# 002_ESP32.net
KiCad netlist of a schematic drawn in Altium Designer
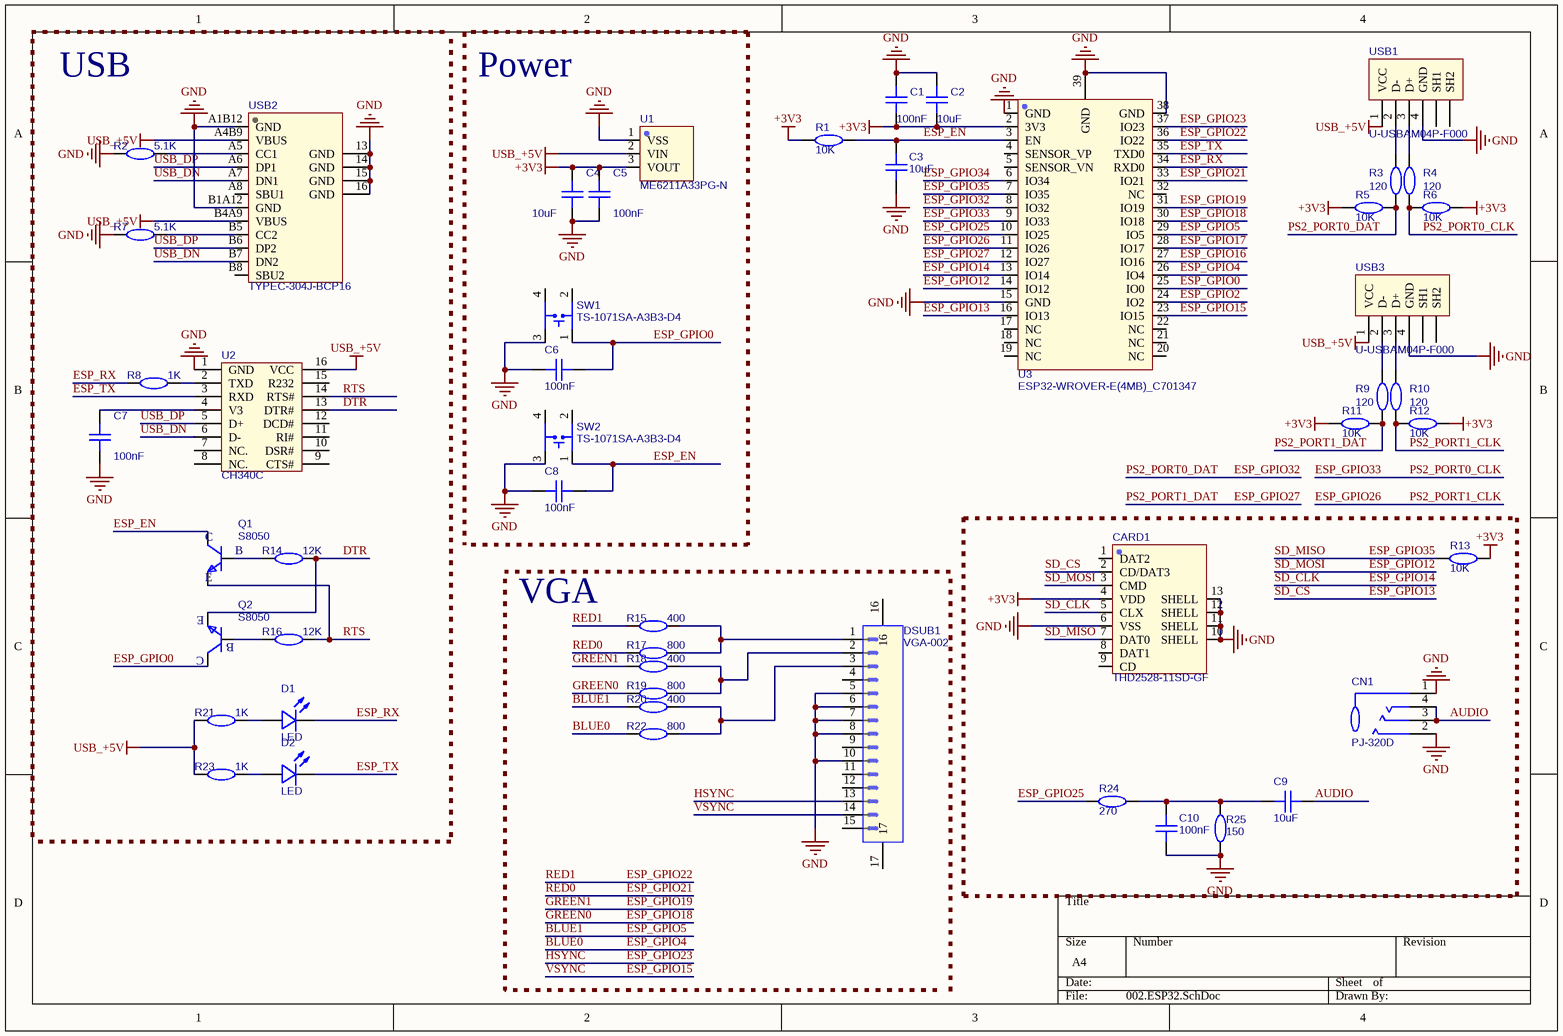
[diagram p0: 002.ESP32.SchDoc]

(export (version "E")
  (design (tool "Eeschema 10.0.6"))
  (components
    (comp (ref "C1")
      (value "100nF")
      (footprint "C0603")
      (fields
        (field (name "BOM_SUPPLIER PART") "C325469")
        (field (name "BOM_MANUFACTURER PART") "CC0603GRNPO9BN200")
        (field (name "CONTRIBUTOR") "LCSC")
      )
      (libsource (lib "miscpcb") (part "CAP_0603"))
    )
    (comp (ref "C2")
      (value "10uF")
      (footprint "C0603")
      (fields
        (field (name "BOM_SUPPLIER PART") "C325469")
        (field (name "BOM_MANUFACTURER PART") "CC0603GRNPO9BN200")
        (field (name "CONTRIBUTOR") "LCSC")
      )
      (libsource (lib "miscpcb") (part "CAP_0603"))
    )
    (comp (ref "C3")
      (value "10uF")
      (footprint "C0603")
      (fields
        (field (name "BOM_SUPPLIER PART") "C325469")
        (field (name "BOM_MANUFACTURER PART") "CC0603GRNPO9BN200")
        (field (name "CONTRIBUTOR") "LCSC")
      )
      (libsource (lib "miscpcb") (part "CAP_0603"))
    )
    (comp (ref "C4")
      (value "10uF")
      (footprint "C0603")
      (fields
        (field (name "BOM_SUPPLIER PART") "C325469")
        (field (name "BOM_MANUFACTURER PART") "CC0603GRNPO9BN200")
        (field (name "CONTRIBUTOR") "LCSC")
      )
      (libsource (lib "miscpcb") (part "CAP_0603"))
    )
    (comp (ref "C5")
      (value "100nF")
      (footprint "C0603")
      (fields
        (field (name "BOM_SUPPLIER PART") "C325469")
        (field (name "BOM_MANUFACTURER PART") "CC0603GRNPO9BN200")
        (field (name "CONTRIBUTOR") "LCSC")
      )
      (libsource (lib "miscpcb") (part "CAP_0603"))
    )
    (comp (ref "C6")
      (value "100nF")
      (footprint "C0603")
      (fields
        (field (name "BOM_SUPPLIER PART") "C325469")
        (field (name "BOM_MANUFACTURER PART") "CC0603GRNPO9BN200")
        (field (name "CONTRIBUTOR") "LCSC")
      )
      (libsource (lib "miscpcb") (part "CAP_0603"))
    )
    (comp (ref "C7")
      (value "100nF")
      (footprint "C0603")
      (fields
        (field (name "BOM_SUPPLIER PART") "C325469")
        (field (name "BOM_MANUFACTURER PART") "CC0603GRNPO9BN200")
        (field (name "CONTRIBUTOR") "LCSC")
      )
      (libsource (lib "miscpcb") (part "CAP_0603"))
    )
    (comp (ref "C8")
      (value "100nF")
      (footprint "C0603")
      (fields
        (field (name "BOM_SUPPLIER PART") "C325469")
        (field (name "BOM_MANUFACTURER PART") "CC0603GRNPO9BN200")
        (field (name "CONTRIBUTOR") "LCSC")
      )
      (libsource (lib "miscpcb") (part "CAP_0603"))
    )
    (comp (ref "C9")
      (value "10uF")
      (footprint "C0603")
      (fields
        (field (name "BOM_SUPPLIER PART") "C325469")
        (field (name "BOM_MANUFACTURER PART") "CC0603GRNPO9BN200")
        (field (name "CONTRIBUTOR") "LCSC")
      )
      (libsource (lib "miscpcb") (part "CAP_0603"))
    )
    (comp (ref "C10")
      (value "100nF")
      (footprint "C0603")
      (fields
        (field (name "BOM_SUPPLIER PART") "C325469")
        (field (name "BOM_MANUFACTURER PART") "CC0603GRNPO9BN200")
        (field (name "CONTRIBUTOR") "LCSC")
      )
      (libsource (lib "miscpcb") (part "CAP_0603"))
    )
    (comp (ref "CARD1")
      (value "THD2528-11SD-GF")
      (footprint "TF-SMD_THD2528-11SD-GF")
      (fields (field (name "BOM_SUPPLIER PART") "C283232") (field (name "CONTRIBUTOR") "LCSC"))
      (libsource (lib "esp32") (part "THD2528-11SD-GF"))
    )
    (comp (ref "CN1")
      (value "PJ-320D")
      (footprint "AUDIO-SMD_PJ-320D")
      (fields (field (name "BOM_SUPPLIER PART") "C431535") (field (name "CONTRIBUTOR") "LCSC"))
      (libsource (lib "esp32") (part "PJ-320D"))
    )
    (comp (ref "D1")
      (value "LED")
      (footprint "LED-0603")
      (fields (field (name "BOM_MANUFACTURER PART") "?"))
      (libsource (lib "miscpcb") (part "LED-Y"))
    )
    (comp (ref "D2")
      (value "LED")
      (footprint "LED-0603")
      (fields (field (name "BOM_MANUFACTURER PART") "?"))
      (libsource (lib "miscpcb") (part "LED-Y"))
    )
    (comp (ref "DSUB1")
      (value "VGA-002")
      (footprint "D-SUB-TH_VGA-002")
      (fields (field (name "BOM_SUPPLIER PART") "C138387"))
      (libsource (lib "esp32") (part "VGA-002"))
    )
    (comp (ref "Q1")
      (value "S8050")
      (footprint "SOT-23_L2.9-W1.3-P0.95-LS2.4-BR")
      (fields (field (name "BOM_SUPPLIER PART") "C414195") (field (name "CONTRIBUTOR") "LCSC"))
      (libsource (lib "miscpcb") (part "S8050"))
    )
    (comp (ref "Q2")
      (value "S8050")
      (footprint "SOT-23_L2.9-W1.3-P0.95-LS2.4-BR")
      (fields (field (name "BOM_SUPPLIER PART") "C414195") (field (name "CONTRIBUTOR") "LCSC"))
      (libsource (lib "miscpcb") (part "S8050"))
    )
    (comp (ref "R1")
      (value "10K")
      (footprint "R0603")
      (fields
        (field (name "BOM_MANUFACTURER PART") "CR0603JA0301G")
        (field (name "BOM_SUPPLIER PART") "C101323")
      )
      (libsource (lib "miscpcb") (part "RES_0603"))
    )
    (comp (ref "R2")
      (value "5.1K")
      (footprint "R0603")
      (fields
        (field (name "BOM_MANUFACTURER PART") "CR0603JA0301G")
        (field (name "BOM_SUPPLIER PART") "C101323")
      )
      (libsource (lib "miscpcb") (part "RES_0603"))
    )
    (comp (ref "R3")
      (value "120")
      (footprint "R0603")
      (fields
        (field (name "BOM_MANUFACTURER PART") "CR0603JA0301G")
        (field (name "BOM_SUPPLIER PART") "C101323")
      )
      (libsource (lib "miscpcb") (part "RES_0603"))
    )
    (comp (ref "R4")
      (value "120")
      (footprint "R0603")
      (fields
        (field (name "BOM_MANUFACTURER PART") "CR0603JA0301G")
        (field (name "BOM_SUPPLIER PART") "C101323")
      )
      (libsource (lib "miscpcb") (part "RES_0603"))
    )
    (comp (ref "R5")
      (value "10K")
      (footprint "R0603")
      (fields
        (field (name "BOM_MANUFACTURER PART") "CR0603JA0301G")
        (field (name "BOM_SUPPLIER PART") "C101323")
      )
      (libsource (lib "miscpcb") (part "RES_0603"))
    )
    (comp (ref "R6")
      (value "10K")
      (footprint "R0603")
      (fields
        (field (name "BOM_MANUFACTURER PART") "CR0603JA0301G")
        (field (name "BOM_SUPPLIER PART") "C101323")
      )
      (libsource (lib "miscpcb") (part "RES_0603"))
    )
    (comp (ref "R7")
      (value "5.1K")
      (footprint "R0603")
      (fields
        (field (name "BOM_MANUFACTURER PART") "CR0603JA0301G")
        (field (name "BOM_SUPPLIER PART") "C101323")
      )
      (libsource (lib "miscpcb") (part "RES_0603"))
    )
    (comp (ref "R8")
      (value "1K")
      (footprint "R0603")
      (fields
        (field (name "BOM_MANUFACTURER PART") "CR0603JA0301G")
        (field (name "BOM_SUPPLIER PART") "C101323")
      )
      (libsource (lib "miscpcb") (part "RES_0603"))
    )
    (comp (ref "R9")
      (value "120")
      (footprint "R0603")
      (fields
        (field (name "BOM_MANUFACTURER PART") "CR0603JA0301G")
        (field (name "BOM_SUPPLIER PART") "C101323")
      )
      (libsource (lib "miscpcb") (part "RES_0603"))
    )
    (comp (ref "R10")
      (value "120")
      (footprint "R0603")
      (fields
        (field (name "BOM_MANUFACTURER PART") "CR0603JA0301G")
        (field (name "BOM_SUPPLIER PART") "C101323")
      )
      (libsource (lib "miscpcb") (part "RES_0603"))
    )
    (comp (ref "R11")
      (value "10K")
      (footprint "R0603")
      (fields
        (field (name "BOM_MANUFACTURER PART") "CR0603JA0301G")
        (field (name "BOM_SUPPLIER PART") "C101323")
      )
      (libsource (lib "miscpcb") (part "RES_0603"))
    )
    (comp (ref "R12")
      (value "10K")
      (footprint "R0603")
      (fields
        (field (name "BOM_MANUFACTURER PART") "CR0603JA0301G")
        (field (name "BOM_SUPPLIER PART") "C101323")
      )
      (libsource (lib "miscpcb") (part "RES_0603"))
    )
    (comp (ref "R13")
      (value "10K")
      (footprint "R0603")
      (fields
        (field (name "BOM_MANUFACTURER PART") "CR0603JA0301G")
        (field (name "BOM_SUPPLIER PART") "C101323")
      )
      (libsource (lib "miscpcb") (part "RES_0603"))
    )
    (comp (ref "R14")
      (value "12K")
      (footprint "R0603")
      (fields
        (field (name "BOM_MANUFACTURER PART") "CR0603JA0301G")
        (field (name "BOM_SUPPLIER PART") "C101323")
      )
      (libsource (lib "miscpcb") (part "RES_0603"))
    )
    (comp (ref "R15")
      (value "400")
      (footprint "R0603")
      (fields
        (field (name "BOM_MANUFACTURER PART") "CR0603JA0301G")
        (field (name "BOM_SUPPLIER PART") "C101323")
      )
      (libsource (lib "miscpcb") (part "RES_0603"))
    )
    (comp (ref "R16")
      (value "12K")
      (footprint "R0603")
      (fields
        (field (name "BOM_MANUFACTURER PART") "CR0603JA0301G")
        (field (name "BOM_SUPPLIER PART") "C101323")
      )
      (libsource (lib "miscpcb") (part "RES_0603"))
    )
    (comp (ref "R17")
      (value "800")
      (footprint "R0603")
      (fields
        (field (name "BOM_MANUFACTURER PART") "CR0603JA0301G")
        (field (name "BOM_SUPPLIER PART") "C101323")
      )
      (libsource (lib "miscpcb") (part "RES_0603"))
    )
    (comp (ref "R18")
      (value "400")
      (footprint "R0603")
      (fields
        (field (name "BOM_MANUFACTURER PART") "CR0603JA0301G")
        (field (name "BOM_SUPPLIER PART") "C101323")
      )
      (libsource (lib "miscpcb") (part "RES_0603"))
    )
    (comp (ref "R19")
      (value "800")
      (footprint "R0603")
      (fields
        (field (name "BOM_MANUFACTURER PART") "CR0603JA0301G")
        (field (name "BOM_SUPPLIER PART") "C101323")
      )
      (libsource (lib "miscpcb") (part "RES_0603"))
    )
    (comp (ref "R20")
      (value "400")
      (footprint "R0603")
      (fields
        (field (name "BOM_MANUFACTURER PART") "CR0603JA0301G")
        (field (name "BOM_SUPPLIER PART") "C101323")
      )
      (libsource (lib "miscpcb") (part "RES_0603"))
    )
    (comp (ref "R21")
      (value "1K")
      (footprint "R0603")
      (fields
        (field (name "BOM_MANUFACTURER PART") "CR0603JA0301G")
        (field (name "BOM_SUPPLIER PART") "C101323")
      )
      (libsource (lib "miscpcb") (part "RES_0603"))
    )
    (comp (ref "R22")
      (value "800")
      (footprint "R0603")
      (fields
        (field (name "BOM_MANUFACTURER PART") "CR0603JA0301G")
        (field (name "BOM_SUPPLIER PART") "C101323")
      )
      (libsource (lib "miscpcb") (part "RES_0603"))
    )
    (comp (ref "R23")
      (value "1K")
      (footprint "R0603")
      (fields
        (field (name "BOM_MANUFACTURER PART") "CR0603JA0301G")
        (field (name "BOM_SUPPLIER PART") "C101323")
      )
      (libsource (lib "miscpcb") (part "RES_0603"))
    )
    (comp (ref "R24")
      (value "270")
      (footprint "R0603")
      (fields
        (field (name "BOM_MANUFACTURER PART") "CR0603JA0301G")
        (field (name "BOM_SUPPLIER PART") "C101323")
      )
      (libsource (lib "miscpcb") (part "RES_0603"))
    )
    (comp (ref "R25")
      (value "150")
      (footprint "R0603")
      (fields
        (field (name "BOM_MANUFACTURER PART") "CR0603JA0301G")
        (field (name "BOM_SUPPLIER PART") "C101323")
      )
      (libsource (lib "miscpcb") (part "RES_0603"))
    )
    (comp (ref "SW1")
      (value "TS-1071SA-A3B3-D4")
      (footprint "KEY-SMD_4P-L3.5-W3.0-P1.40-LS4.6")
      (fields (field (name "BOM_SUPPLIER PART") "C498309") (field (name "CONTRIBUTOR") "LCSC"))
      (libsource (lib "esp32") (part "TS-1071SA-A3B3-D4"))
    )
    (comp (ref "SW2")
      (value "TS-1071SA-A3B3-D4")
      (footprint "KEY-SMD_4P-L3.5-W3.0-P1.40-LS4.6")
      (fields (field (name "BOM_SUPPLIER PART") "C498309") (field (name "CONTRIBUTOR") "LCSC"))
      (libsource (lib "esp32") (part "TS-1071SA-A3B3-D4"))
    )
    (comp (ref "U1")
      (value "ME6211A33PG-N")
      (footprint "SOT-89_L4.5-W2.5-P1.50-LS4.2-BR")
      (fields (field (name "BOM_SUPPLIER PART") "C236673") (field (name "CONTRIBUTOR") "LCSC"))
      (libsource (lib "esp32") (part "ME6211A33PG-N"))
    )
    (comp (ref "U2")
      (value "CH340C")
      (footprint "SOP-16_L10.0-W3.9-P1.27-LS6.0-BL")
      (fields (field (name "BOM_SUPPLIER PART") "C84681"))
      (libsource (lib "esp32") (part "CH340C"))
    )
    (comp (ref "U3")
      (value "ESP32-WROVER-E(4MB)_C701347")
      (footprint "WIFI-SMD_ESP32-WROVER-E")
      (fields
        (field (name "BOM_SUPPLIER PART") "C701347")
        (field (name "BOM_MANUFACTURER PART") "ESP32-WROVER-E(4MB)")
        (field (name "CONTRIBUTOR") "LCSC")
      )
      (libsource (lib "esp32") (part "ESP32-WROVER-E(4MB)_C701347"))
    )
    (comp (ref "USB1")
      (value "U-USBAM04P-F000")
      (footprint "USB-A-SMD_U-USBAM04P-F000")
      (fields (field (name "BOM_SUPPLIER PART") "C386738") (field (name "CONTRIBUTOR") "LCSC"))
      (libsource (lib "esp32") (part "U-USBAM04P-F000"))
    )
    (comp (ref "USB2")
      (value "TYPEC-304J-BCP16")
      (footprint "USB-C-SMD_TYPEC-304J-BCP16")
      (fields (field (name "BOM_SUPPLIER PART") "C2835315") (field (name "CONTRIBUTOR") "LCSC"))
      (libsource (lib "esp32") (part "TYPEC-304J-BCP16"))
    )
    (comp (ref "USB3")
      (value "U-USBAM04P-F000")
      (footprint "USB-A-SMD_U-USBAM04P-F000")
      (fields (field (name "BOM_SUPPLIER PART") "C386738") (field (name "CONTRIBUTOR") "LCSC"))
      (libsource (lib "esp32") (part "U-USBAM04P-F000"))
    )
  )
  (nets
    (net (code "1") (name "+3V3") (class "Default")
      (node (ref "C1") (pin "2") (pinfunction "2_2") (pintype "passive"))
      (node (ref "C2") (pin "2") (pinfunction "2_2") (pintype "passive"))
      (node (ref "C4") (pin "2") (pinfunction "2_2") (pintype "passive"))
      (node (ref "C5") (pin "2") (pinfunction "2_2") (pintype "passive"))
      (node (ref "CARD1") (pin "4") (pinfunction "VDD_4") (pintype "passive"))
      (node (ref "R1") (pin "1") (pinfunction "1_1") (pintype "passive"))
      (node (ref "R11") (pin "2") (pinfunction "2_2") (pintype "passive"))
      (node (ref "R12") (pin "1") (pinfunction "1_1") (pintype "passive"))
      (node (ref "R13") (pin "1") (pinfunction "1_1") (pintype "passive"))
      (node (ref "R5") (pin "2") (pinfunction "2_2") (pintype "passive"))
      (node (ref "R6") (pin "1") (pinfunction "1_1") (pintype "passive"))
      (node (ref "U1") (pin "3") (pinfunction "VOUT_3") (pintype "passive"))
      (node (ref "U3") (pin "2") (pinfunction "3V3_2") (pintype "passive"))
    )
    (net (code "2") (name "/AUDIO") (class "Default")
      (node (ref "C9") (pin "1") (pinfunction "1_1") (pintype "passive"))
      (node (ref "CN1") (pin "3") (pinfunction "3_3") (pintype "passive"))
      (node (ref "CN1") (pin "4") (pinfunction "4_4") (pintype "passive"))
    )
    (net (code "3") (name "/BLUE0") (class "Default")
      (node (ref "R22") (pin "2") (pinfunction "2_2") (pintype "passive"))
      (node (ref "U3") (pin "26") (pinfunction "IO4_26") (pintype "passive"))
    )
    (net (code "4") (name "/BLUE1") (class "Default")
      (node (ref "R20") (pin "2") (pinfunction "2_2") (pintype "passive"))
      (node (ref "U3") (pin "29") (pinfunction "IO5_29") (pintype "passive"))
    )
    (net (code "5") (name "/DTR") (class "Default")
      (node (ref "Q2") (pin "2") (pinfunction "E_2") (pintype "passive"))
      (node (ref "R14") (pin "1") (pinfunction "1_1") (pintype "passive"))
      (node (ref "U2") (pin "13") (pinfunction "DTR#_13") (pintype "passive"))
    )
    (net (code "6") (name "/ESP_EN") (class "Default")
      (node (ref "C3") (pin "1") (pinfunction "1_1") (pintype "passive"))
      (node (ref "C8") (pin "1") (pinfunction "1_1") (pintype "passive"))
      (node (ref "Q1") (pin "3") (pinfunction "C_3") (pintype "passive"))
      (node (ref "R1") (pin "2") (pinfunction "2_2") (pintype "passive"))
      (node (ref "SW2") (pin "1") (pinfunction "1_1") (pintype "passive"))
      (node (ref "U3") (pin "3") (pinfunction "EN_3") (pintype "passive"))
    )
    (net (code "7") (name "/ESP_GPIO0") (class "Default")
      (node (ref "C6") (pin "1") (pinfunction "1_1") (pintype "passive"))
      (node (ref "Q2") (pin "3") (pinfunction "C_3") (pintype "passive"))
      (node (ref "SW1") (pin "1") (pinfunction "1_1") (pintype "passive"))
      (node (ref "U3") (pin "25") (pinfunction "IO0_25") (pintype "passive"))
    )
    (net (code "8") (name "/ESP_GPIO2") (class "Default")
      (node (ref "U3") (pin "24") (pinfunction "IO2_24") (pintype "passive"))
    )
    (net (code "9") (name "/ESP_GPIO12") (class "Default")
      (node (ref "CARD1") (pin "3") (pinfunction "CMD_3") (pintype "passive"))
      (node (ref "U3") (pin "14") (pinfunction "IO12_14") (pintype "passive"))
    )
    (net (code "10") (name "/ESP_GPIO13") (class "Default")
      (node (ref "CARD1") (pin "2") (pinfunction "CD/DAT3_2") (pintype "passive"))
      (node (ref "U3") (pin "16") (pinfunction "IO13_16") (pintype "passive"))
    )
    (net (code "11") (name "/ESP_GPIO14") (class "Default")
      (node (ref "CARD1") (pin "5") (pinfunction "CLX_5") (pintype "passive"))
      (node (ref "U3") (pin "13") (pinfunction "IO14_13") (pintype "passive"))
    )
    (net (code "12") (name "/ESP_GPIO15") (class "Default")
      (node (ref "DSUB1") (pin "14") (pinfunction "14_14") (pintype "passive"))
      (node (ref "U3") (pin "23") (pinfunction "IO15_23") (pintype "passive"))
    )
    (net (code "13") (name "/ESP_GPIO16") (class "Default")
      (node (ref "U3") (pin "27") (pinfunction "IO16_27") (pintype "passive"))
    )
    (net (code "14") (name "/ESP_GPIO17") (class "Default")
      (node (ref "U3") (pin "28") (pinfunction "IO17_28") (pintype "passive"))
    )
    (net (code "15") (name "/ESP_GPIO18") (class "Default")
      (node (ref "R19") (pin "2") (pinfunction "2_2") (pintype "passive"))
      (node (ref "U3") (pin "30") (pinfunction "IO18_30") (pintype "passive"))
    )
    (net (code "16") (name "/ESP_GPIO19") (class "Default")
      (node (ref "R18") (pin "2") (pinfunction "2_2") (pintype "passive"))
      (node (ref "U3") (pin "31") (pinfunction "IO19_31") (pintype "passive"))
    )
    (net (code "17") (name "/ESP_GPIO21") (class "Default")
      (node (ref "R17") (pin "2") (pinfunction "2_2") (pintype "passive"))
      (node (ref "U3") (pin "33") (pinfunction "IO21_33") (pintype "passive"))
    )
    (net (code "18") (name "/ESP_GPIO22") (class "Default")
      (node (ref "R15") (pin "2") (pinfunction "2_2") (pintype "passive"))
      (node (ref "U3") (pin "36") (pinfunction "IO22_36") (pintype "passive"))
    )
    (net (code "19") (name "/ESP_GPIO23") (class "Default")
      (node (ref "DSUB1") (pin "13") (pinfunction "13_13") (pintype "passive"))
      (node (ref "U3") (pin "37") (pinfunction "IO23_37") (pintype "passive"))
    )
    (net (code "20") (name "/ESP_GPIO25") (class "Default")
      (node (ref "R24") (pin "2") (pinfunction "2_2") (pintype "passive"))
      (node (ref "U3") (pin "10") (pinfunction "IO25_10") (pintype "passive"))
    )
    (net (code "21") (name "/ESP_GPIO26") (class "Default")
      (node (ref "R10") (pin "2") (pinfunction "2_2") (pintype "passive"))
      (node (ref "R12") (pin "2") (pinfunction "2_2") (pintype "passive"))
      (node (ref "U3") (pin "11") (pinfunction "IO26_11") (pintype "passive"))
    )
    (net (code "22") (name "/ESP_GPIO27") (class "Default")
      (node (ref "R11") (pin "1") (pinfunction "1_1") (pintype "passive"))
      (node (ref "R9") (pin "2") (pinfunction "2_2") (pintype "passive"))
      (node (ref "U3") (pin "12") (pinfunction "IO27_12") (pintype "passive"))
    )
    (net (code "23") (name "/ESP_GPIO32") (class "Default")
      (node (ref "R3") (pin "2") (pinfunction "2_2") (pintype "passive"))
      (node (ref "R5") (pin "1") (pinfunction "1_1") (pintype "passive"))
      (node (ref "U3") (pin "8") (pinfunction "IO32_8") (pintype "passive"))
    )
    (net (code "24") (name "/ESP_GPIO33") (class "Default")
      (node (ref "R4") (pin "2") (pinfunction "2_2") (pintype "passive"))
      (node (ref "R6") (pin "2") (pinfunction "2_2") (pintype "passive"))
      (node (ref "U3") (pin "9") (pinfunction "IO33_9") (pintype "passive"))
    )
    (net (code "25") (name "/ESP_GPIO34") (class "Default")
      (node (ref "U3") (pin "6") (pinfunction "IO34_6") (pintype "passive"))
    )
    (net (code "26") (name "/ESP_GPIO35") (class "Default")
      (node (ref "CARD1") (pin "7") (pinfunction "DAT0_7") (pintype "passive"))
      (node (ref "R13") (pin "2") (pinfunction "2_2") (pintype "passive"))
      (node (ref "U3") (pin "7") (pinfunction "IO35_7") (pintype "passive"))
    )
    (net (code "27") (name "/ESP_RX") (class "Default")
      (node (ref "D1") (pin "2") (pinfunction "K_2") (pintype "passive"))
      (node (ref "R8") (pin "2") (pinfunction "2_2") (pintype "passive"))
      (node (ref "U3") (pin "34") (pinfunction "RXD0_34") (pintype "passive"))
    )
    (net (code "28") (name "/ESP_TX") (class "Default")
      (node (ref "D2") (pin "2") (pinfunction "K_2") (pintype "passive"))
      (node (ref "U2") (pin "3") (pinfunction "RXD_3") (pintype "passive"))
      (node (ref "U3") (pin "35") (pinfunction "TXD0_35") (pintype "passive"))
    )
    (net (code "29") (name "/RTS") (class "Default")
      (node (ref "Q1") (pin "2") (pinfunction "E_2") (pintype "passive"))
      (node (ref "R16") (pin "1") (pinfunction "1_1") (pintype "passive"))
      (node (ref "U2") (pin "14") (pinfunction "RTS#_14") (pintype "passive"))
    )
    (net (code "30") (name "/USB_DN") (class "Default")
      (node (ref "U2") (pin "6") (pinfunction "D-_6") (pintype "passive"))
      (node (ref "USB2") (pin "A7") (pinfunction "DN1_A7") (pintype "passive"))
      (node (ref "USB2") (pin "B7") (pinfunction "DN2_B7") (pintype "passive"))
    )
    (net (code "31") (name "/USB_DP") (class "Default")
      (node (ref "U2") (pin "5") (pinfunction "D+_5") (pintype "passive"))
      (node (ref "USB2") (pin "A6") (pinfunction "DP1_A6") (pintype "passive"))
      (node (ref "USB2") (pin "B6") (pinfunction "DP2_B6") (pintype "passive"))
    )
    (net (code "32") (name "GND") (class "Default")
      (node (ref "C1") (pin "1") (pinfunction "1_1") (pintype "passive"))
      (node (ref "C10") (pin "1") (pinfunction "1_1") (pintype "passive"))
      (node (ref "C2") (pin "1") (pinfunction "1_1") (pintype "passive"))
      (node (ref "C3") (pin "2") (pinfunction "2_2") (pintype "passive"))
      (node (ref "C4") (pin "1") (pinfunction "1_1") (pintype "passive"))
      (node (ref "C5") (pin "1") (pinfunction "1_1") (pintype "passive"))
      (node (ref "C6") (pin "2") (pinfunction "2_2") (pintype "passive"))
      (node (ref "C7") (pin "1") (pinfunction "1_1") (pintype "passive"))
      (node (ref "C8") (pin "2") (pinfunction "2_2") (pintype "passive"))
      (node (ref "CARD1") (pin "10") (pinfunction "SHELL_10") (pintype "passive"))
      (node (ref "CARD1") (pin "11") (pinfunction "SHELL_11") (pintype "passive"))
      (node (ref "CARD1") (pin "12") (pinfunction "SHELL_12") (pintype "passive"))
      (node (ref "CARD1") (pin "13") (pinfunction "SHELL_13") (pintype "passive"))
      (node (ref "CARD1") (pin "6") (pinfunction "VSS_6") (pintype "passive"))
      (node (ref "CN1") (pin "1") (pinfunction "1_1") (pintype "passive"))
      (node (ref "CN1") (pin "2") (pinfunction "2_2") (pintype "passive"))
      (node (ref "DSUB1") (pin "10") (pinfunction "10_10") (pintype "passive"))
      (node (ref "DSUB1") (pin "5") (pinfunction "5_5") (pintype "passive"))
      (node (ref "DSUB1") (pin "6") (pinfunction "6_6") (pintype "passive"))
      (node (ref "DSUB1") (pin "7") (pinfunction "7_7") (pintype "passive"))
      (node (ref "DSUB1") (pin "8") (pinfunction "8_8") (pintype "passive"))
      (node (ref "R2") (pin "2") (pinfunction "2_2") (pintype "passive"))
      (node (ref "R25") (pin "2") (pinfunction "2_2") (pintype "passive"))
      (node (ref "R7") (pin "2") (pinfunction "2_2") (pintype "passive"))
      (node (ref "SW1") (pin "3") (pinfunction "3_3") (pintype "passive"))
      (node (ref "SW2") (pin "3") (pinfunction "3_3") (pintype "passive"))
      (node (ref "U1") (pin "1") (pinfunction "VSS_1") (pintype "passive"))
      (node (ref "U2") (pin "1") (pinfunction "GND_1") (pintype "passive"))
      (node (ref "U3") (pin "1") (pinfunction "GND_1") (pintype "passive"))
      (node (ref "U3") (pin "15") (pinfunction "GND_15") (pintype "passive"))
      (node (ref "U3") (pin "38") (pinfunction "GND_38") (pintype "passive"))
      (node (ref "U3") (pin "39") (pinfunction "GND_39") (pintype "passive"))
      (node (ref "USB1") (pin "4") (pinfunction "GND_4") (pintype "passive"))
      (node (ref "USB2") (pin "13") (pinfunction "GND_13") (pintype "passive"))
      (node (ref "USB2") (pin "14") (pinfunction "GND_14") (pintype "passive"))
      (node (ref "USB2") (pin "15") (pinfunction "GND_15") (pintype "passive"))
      (node (ref "USB2") (pin "16") (pinfunction "GND_16") (pintype "passive"))
      (node (ref "USB2") (pin "A1B12") (pinfunction "GND_A1B12") (pintype "passive"))
      (node (ref "USB2") (pin "B1A12") (pinfunction "GND_B1A12") (pintype "passive"))
      (node (ref "USB3") (pin "4") (pinfunction "GND_4") (pintype "passive"))
    )
    (net (code "33") (name "Net-(C10-Pad2)") (class "Default")
      (node (ref "C10") (pin "2") (pinfunction "2_2") (pintype "passive"))
      (node (ref "C9") (pin "2") (pinfunction "2_2") (pintype "passive"))
      (node (ref "R24") (pin "1") (pinfunction "1_1") (pintype "passive"))
      (node (ref "R25") (pin "1") (pinfunction "1_1") (pintype "passive"))
    )
    (net (code "34") (name "Net-(D1-A)") (class "Default")
      (node (ref "D1") (pin "1") (pinfunction "A_1") (pintype "passive"))
      (node (ref "R21") (pin "1") (pinfunction "1_1") (pintype "passive"))
    )
    (net (code "35") (name "Net-(D2-A)") (class "Default")
      (node (ref "D2") (pin "1") (pinfunction "A_1") (pintype "passive"))
      (node (ref "R23") (pin "1") (pinfunction "1_1") (pintype "passive"))
    )
    (net (code "36") (name "Net-(DSUB1-Pad1)") (class "Default")
      (node (ref "DSUB1") (pin "1") (pinfunction "1_1") (pintype "passive"))
      (node (ref "R15") (pin "1") (pinfunction "1_1") (pintype "passive"))
      (node (ref "R17") (pin "1") (pinfunction "1_1") (pintype "passive"))
    )
    (net (code "37") (name "Net-(DSUB1-Pad2)") (class "Default")
      (node (ref "DSUB1") (pin "2") (pinfunction "2_2") (pintype "passive"))
      (node (ref "R18") (pin "1") (pinfunction "1_1") (pintype "passive"))
      (node (ref "R19") (pin "1") (pinfunction "1_1") (pintype "passive"))
    )
    (net (code "38") (name "Net-(DSUB1-Pad3)") (class "Default")
      (node (ref "DSUB1") (pin "3") (pinfunction "3_3") (pintype "passive"))
      (node (ref "R20") (pin "1") (pinfunction "1_1") (pintype "passive"))
      (node (ref "R22") (pin "1") (pinfunction "1_1") (pintype "passive"))
    )
    (net (code "39") (name "Net-(Q1-B)") (class "Default")
      (node (ref "Q1") (pin "1") (pinfunction "B_1") (pintype "passive"))
      (node (ref "R14") (pin "2") (pinfunction "2_2") (pintype "passive"))
    )
    (net (code "40") (name "Net-(Q2-B)") (class "Default")
      (node (ref "Q2") (pin "1") (pinfunction "B_1") (pintype "passive"))
      (node (ref "R16") (pin "2") (pinfunction "2_2") (pintype "passive"))
    )
    (net (code "41") (name "Net-(U2-TXD)") (class "Default")
      (node (ref "R8") (pin "1") (pinfunction "1_1") (pintype "passive"))
      (node (ref "U2") (pin "2") (pinfunction "TXD_2") (pintype "passive"))
    )
    (net (code "42") (name "Net-(U2-V3)") (class "Default")
      (node (ref "C7") (pin "2") (pinfunction "2_2") (pintype "passive"))
      (node (ref "U2") (pin "4") (pinfunction "V3_4") (pintype "passive"))
    )
    (net (code "43") (name "Net-(USB1-D+)") (class "Default")
      (node (ref "R4") (pin "1") (pinfunction "1_1") (pintype "passive"))
      (node (ref "USB1") (pin "3") (pinfunction "D+_3") (pintype "passive"))
    )
    (net (code "44") (name "Net-(USB1-D-)") (class "Default")
      (node (ref "R3") (pin "1") (pinfunction "1_1") (pintype "passive"))
      (node (ref "USB1") (pin "2") (pinfunction "D-_2") (pintype "passive"))
    )
    (net (code "45") (name "Net-(USB2-CC1)") (class "Default")
      (node (ref "R2") (pin "1") (pinfunction "1_1") (pintype "passive"))
      (node (ref "USB2") (pin "A5") (pinfunction "CC1_A5") (pintype "passive"))
    )
    (net (code "46") (name "Net-(USB2-CC2)") (class "Default")
      (node (ref "R7") (pin "1") (pinfunction "1_1") (pintype "passive"))
      (node (ref "USB2") (pin "B5") (pinfunction "CC2_B5") (pintype "passive"))
    )
    (net (code "47") (name "Net-(USB3-D+)") (class "Default")
      (node (ref "R10") (pin "1") (pinfunction "1_1") (pintype "passive"))
      (node (ref "USB3") (pin "3") (pinfunction "D+_3") (pintype "passive"))
    )
    (net (code "48") (name "Net-(USB3-D-)") (class "Default")
      (node (ref "R9") (pin "1") (pinfunction "1_1") (pintype "passive"))
      (node (ref "USB3") (pin "2") (pinfunction "D-_2") (pintype "passive"))
    )
    (net (code "49") (name "USB_+5V") (class "Default")
      (node (ref "R21") (pin "2") (pinfunction "2_2") (pintype "passive"))
      (node (ref "R23") (pin "2") (pinfunction "2_2") (pintype "passive"))
      (node (ref "U1") (pin "2") (pinfunction "VIN_2") (pintype "passive"))
      (node (ref "U2") (pin "16") (pinfunction "VCC_16") (pintype "passive"))
      (node (ref "USB1") (pin "1") (pinfunction "VCC_1") (pintype "passive"))
      (node (ref "USB2") (pin "A4B9") (pinfunction "VBUS_A4B9") (pintype "passive"))
      (node (ref "USB2") (pin "B4A9") (pinfunction "VBUS_B4A9") (pintype "passive"))
      (node (ref "USB3") (pin "1") (pinfunction "VCC_1") (pintype "passive"))
    )
    (net (code "50") (name "unconnected-(CARD1-CD-Pad9)") (class "Default")
      (node (ref "CARD1") (pin "9") (pinfunction "CD_9") (pintype "passive"))
    )
    (net (code "51") (name "unconnected-(CARD1-DAT1-Pad8)") (class "Default")
      (node (ref "CARD1") (pin "8") (pinfunction "DAT1_8") (pintype "passive"))
    )
    (net (code "52") (name "unconnected-(CARD1-DAT2-Pad1)") (class "Default")
      (node (ref "CARD1") (pin "1") (pinfunction "DAT2_1") (pintype "passive"))
    )
    (net (code "53") (name "unconnected-(DSUB1-Pad4)") (class "Default")
      (node (ref "DSUB1") (pin "4") (pinfunction "4_4") (pintype "passive"))
    )
    (net (code "54") (name "unconnected-(DSUB1-Pad9)") (class "Default")
      (node (ref "DSUB1") (pin "9") (pinfunction "9_9") (pintype "passive"))
    )
    (net (code "55") (name "unconnected-(DSUB1-Pad11)") (class "Default")
      (node (ref "DSUB1") (pin "11") (pinfunction "11_11") (pintype "passive"))
    )
    (net (code "56") (name "unconnected-(DSUB1-Pad12)") (class "Default")
      (node (ref "DSUB1") (pin "12") (pinfunction "12_12") (pintype "passive"))
    )
    (net (code "57") (name "unconnected-(DSUB1-Pad15)") (class "Default")
      (node (ref "DSUB1") (pin "15") (pinfunction "15_15") (pintype "passive"))
    )
    (net (code "58") (name "unconnected-(DSUB1-Pad16)") (class "Default")
      (node (ref "DSUB1") (pin "16") (pinfunction "16_16") (pintype "passive"))
    )
    (net (code "59") (name "unconnected-(DSUB1-Pad17)") (class "Default")
      (node (ref "DSUB1") (pin "17") (pinfunction "17_17") (pintype "passive"))
    )
    (net (code "60") (name "unconnected-(SW1-Pad2)") (class "Default")
      (node (ref "SW1") (pin "2") (pinfunction "2_2") (pintype "passive"))
    )
    (net (code "61") (name "unconnected-(SW1-Pad4)") (class "Default")
      (node (ref "SW1") (pin "4") (pinfunction "4_4") (pintype "passive"))
    )
    (net (code "62") (name "unconnected-(SW2-Pad2)") (class "Default")
      (node (ref "SW2") (pin "2") (pinfunction "2_2") (pintype "passive"))
    )
    (net (code "63") (name "unconnected-(SW2-Pad4)") (class "Default")
      (node (ref "SW2") (pin "4") (pinfunction "4_4") (pintype "passive"))
    )
    (net (code "64") (name "unconnected-(U2-CTS#-Pad9)") (class "Default")
      (node (ref "U2") (pin "9") (pinfunction "CTS#_9") (pintype "passive"))
    )
    (net (code "65") (name "unconnected-(U2-DCD#-Pad12)") (class "Default")
      (node (ref "U2") (pin "12") (pinfunction "DCD#_12") (pintype "passive"))
    )
    (net (code "66") (name "unconnected-(U2-DSR#-Pad10)") (class "Default")
      (node (ref "U2") (pin "10") (pinfunction "DSR#_10") (pintype "passive"))
    )
    (net (code "67") (name "unconnected-(U2-NC.-Pad7)") (class "Default")
      (node (ref "U2") (pin "7") (pinfunction "NC._7") (pintype "passive"))
    )
    (net (code "68") (name "unconnected-(U2-NC.-Pad8)") (class "Default")
      (node (ref "U2") (pin "8") (pinfunction "NC._8") (pintype "passive"))
    )
    (net (code "69") (name "unconnected-(U2-R232-Pad15)") (class "Default")
      (node (ref "U2") (pin "15") (pinfunction "R232_15") (pintype "passive"))
    )
    (net (code "70") (name "unconnected-(U2-RI#-Pad11)") (class "Default")
      (node (ref "U2") (pin "11") (pinfunction "RI#_11") (pintype "passive"))
    )
    (net (code "71") (name "unconnected-(U3-NC-Pad17)") (class "Default")
      (node (ref "U3") (pin "17") (pinfunction "NC_17") (pintype "passive"))
    )
    (net (code "72") (name "unconnected-(U3-NC-Pad18)") (class "Default")
      (node (ref "U3") (pin "18") (pinfunction "NC_18") (pintype "passive"))
    )
    (net (code "73") (name "unconnected-(U3-NC-Pad19)") (class "Default")
      (node (ref "U3") (pin "19") (pinfunction "NC_19") (pintype "passive"))
    )
    (net (code "74") (name "unconnected-(U3-NC-Pad20)") (class "Default")
      (node (ref "U3") (pin "20") (pinfunction "NC_20") (pintype "passive"))
    )
    (net (code "75") (name "unconnected-(U3-NC-Pad21)") (class "Default")
      (node (ref "U3") (pin "21") (pinfunction "NC_21") (pintype "passive"))
    )
    (net (code "76") (name "unconnected-(U3-NC-Pad22)") (class "Default")
      (node (ref "U3") (pin "22") (pinfunction "NC_22") (pintype "passive"))
    )
    (net (code "77") (name "unconnected-(U3-NC-Pad32)") (class "Default")
      (node (ref "U3") (pin "32") (pinfunction "NC_32") (pintype "passive"))
    )
    (net (code "78") (name "unconnected-(U3-SENSOR_VN-Pad5)") (class "Default")
      (node (ref "U3") (pin "5") (pinfunction "SENSOR_VN_5") (pintype "passive"))
    )
    (net (code "79") (name "unconnected-(U3-SENSOR_VP-Pad4)") (class "Default")
      (node (ref "U3") (pin "4") (pinfunction "SENSOR_VP_4") (pintype "passive"))
    )
    (net (code "80") (name "unconnected-(USB1-PadSH1)") (class "Default")
      (node (ref "USB1") (pin "SH1") (pinfunction "SH1_SH1") (pintype "passive"))
    )
    (net (code "81") (name "unconnected-(USB1-PadSH2)") (class "Default")
      (node (ref "USB1") (pin "SH2") (pinfunction "SH2_SH2") (pintype "passive"))
    )
    (net (code "82") (name "unconnected-(USB2-SBU1-PadA8)") (class "Default")
      (node (ref "USB2") (pin "A8") (pinfunction "SBU1_A8") (pintype "passive"))
    )
    (net (code "83") (name "unconnected-(USB2-SBU2-PadB8)") (class "Default")
      (node (ref "USB2") (pin "B8") (pinfunction "SBU2_B8") (pintype "passive"))
    )
    (net (code "84") (name "unconnected-(USB3-PadSH1)") (class "Default")
      (node (ref "USB3") (pin "SH1") (pinfunction "SH1_SH1") (pintype "passive"))
    )
    (net (code "85") (name "unconnected-(USB3-PadSH2)") (class "Default")
      (node (ref "USB3") (pin "SH2") (pinfunction "SH2_SH2") (pintype "passive"))
    )
  )
)
